# 6_RgbLed.net
KiCad netlist of a schematic drawn in Altium Designer
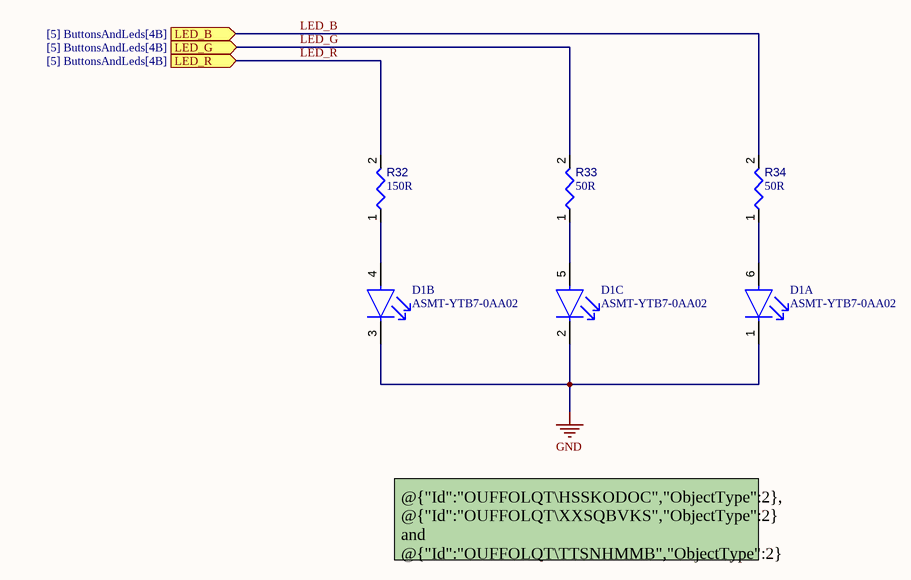
[diagram p0: [6] RgbLed.SchDoc]

(export (version "E")
  (design (tool "Eeschema 10.0.6"))
  (components
    (comp (ref "D1")
      (value "ASMT-YTB7-0AA02")
      (footprint "FP-PLCC-6-MFG")
      (description "LED Tri-Color Blue/Green/Red 469nm/529nm/623nm Chip LED 6-Pin PLCC T/R")
      (libsource (lib "UFCG - Universidade Federal de Campina Grande") (part "0f3d36aaa98356051a15b42400af8f3"))
    )
    (comp (ref "R32")
      (value "150R")
      (footprint "RESC0603(1608)_L")
      (description "SMD Chip Resistor, 150 Ohm, ± 1%, 100 mW, 0603 [1608 Metric], Thick Film, General Purpose")
      (fields (field (name "TOLERANCE") "1%") (field (name "Comment") "CRCW0603150RFKEA"))
      (libsource (lib "UFCG - Universidade Federal de Campina Grande") (part "RES-2"))
    )
    (comp (ref "R33")
      (value "50R")
      (footprint "RESC0603(1608)_L")
      (description "SMD Chip Resistor, 50 Ohm, ± 1%, 100 mW, 0603 [1608 Metric], Thick Film, General Purpose")
      (fields (field (name "TOLERANCE") "1%") (field (name "Comment") "CRCW060350R0FKEA"))
      (libsource (lib "UFCG - Universidade Federal de Campina Grande") (part "RES-2"))
    )
    (comp (ref "R34")
      (value "50R")
      (footprint "RESC0603(1608)_L")
      (description "SMD Chip Resistor, 50 Ohm, ± 1%, 100 mW, 0603 [1608 Metric], Thick Film, General Purpose")
      (fields (field (name "TOLERANCE") "1%") (field (name "Comment") "CRCW060350R0FKEA"))
      (libsource (lib "UFCG - Universidade Federal de Campina Grande") (part "RES-2"))
    )
  )
  (nets
    (net (code "1") (name "/LED_B") (class "Default")
      (node (ref "R34") (pin "2") (pinfunction "2_2") (pintype "passive"))
    )
    (net (code "2") (name "/LED_G") (class "Default")
      (node (ref "R33") (pin "2") (pinfunction "2_2") (pintype "passive"))
    )
    (net (code "3") (name "/LED_R") (class "Default")
      (node (ref "R32") (pin "2") (pinfunction "2_2") (pintype "passive"))
    )
    (net (code "4") (name "GND") (class "Default")
      (node (ref "D1") (pin "1") (pinfunction "Cathode(Blue)_1") (pintype "passive"))
      (node (ref "D1") (pin "2") (pinfunction "Cathode(Green)_2") (pintype "passive"))
      (node (ref "D1") (pin "3") (pinfunction "Cathode(Red)_3") (pintype "passive"))
    )
    (net (code "5") (name "Net-(D1A-Anode(Blue))") (class "Default")
      (node (ref "D1") (pin "6") (pinfunction "Anode(Blue)_6") (pintype "passive"))
      (node (ref "R34") (pin "1") (pinfunction "1_1") (pintype "passive"))
    )
    (net (code "6") (name "Net-(D1B-Anode(Red))") (class "Default")
      (node (ref "D1") (pin "4") (pinfunction "Anode(Red)_4") (pintype "passive"))
      (node (ref "R32") (pin "1") (pinfunction "1_1") (pintype "passive"))
    )
    (net (code "7") (name "Net-(D1C-Anode(Green))") (class "Default")
      (node (ref "D1") (pin "5") (pinfunction "Anode(Green)_5") (pintype "passive"))
      (node (ref "R33") (pin "1") (pinfunction "1_1") (pintype "passive"))
    )
  )
)
